# main_board_smd.net
KiCad netlist of a schematic drawn in EAGLE
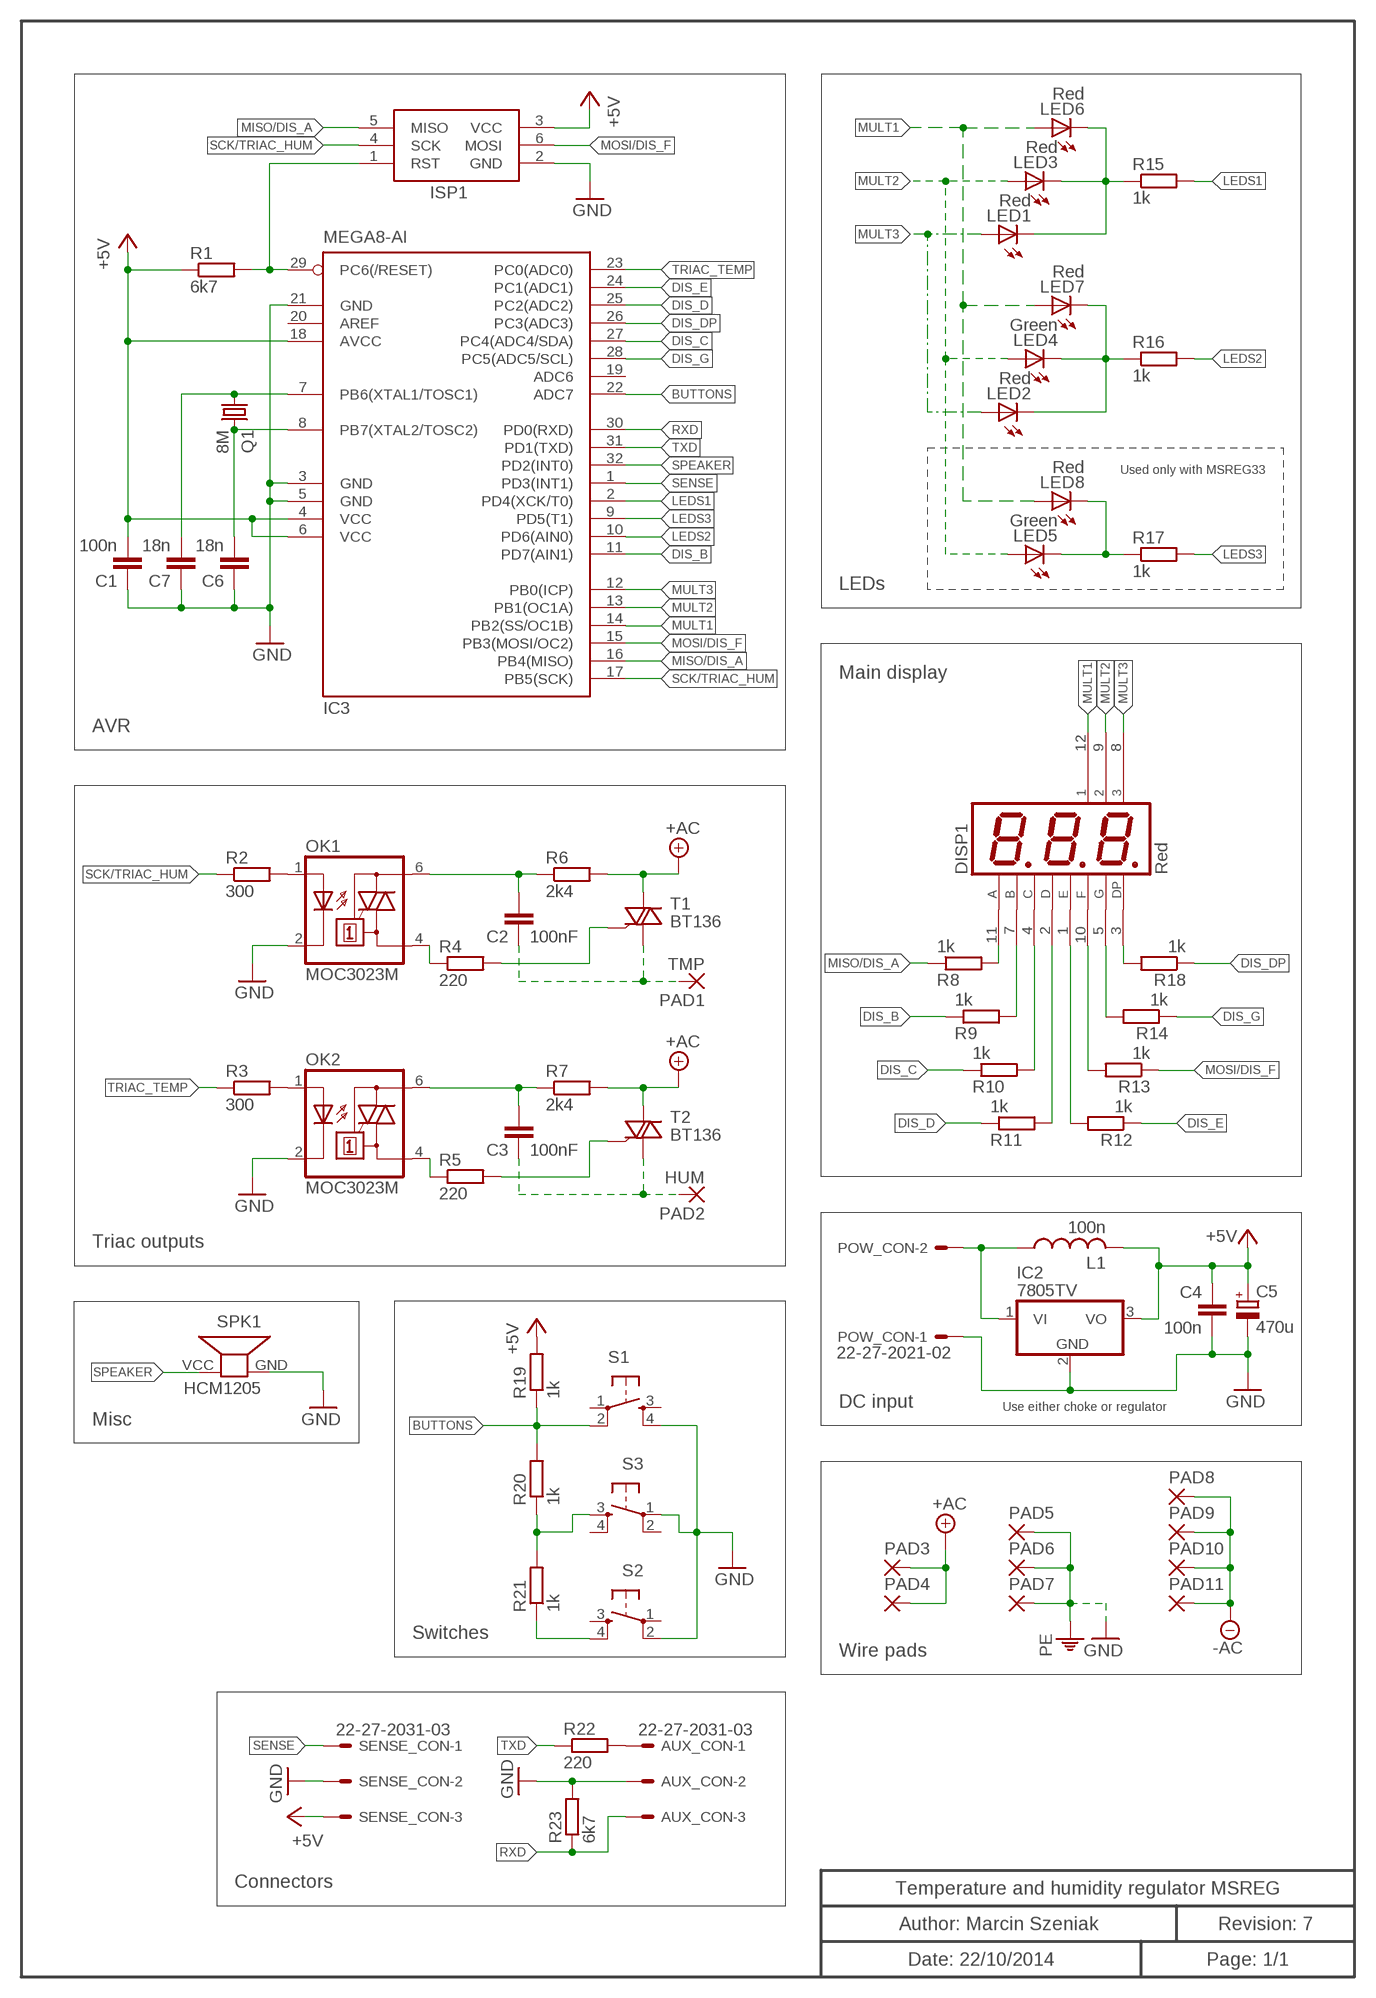
[diagram p0: schematic, sheet 1]

(export (version "E")
  (design (tool "Eeschema 10.0.6"))
  (components
    (comp (ref "AUX_CON")
      (value "22-27-2031-03")
      (footprint "eagle-import:6410-03")
      (libsource (lib "eagle-import") (part "22-?-0327-2031"))
    )
    (comp (ref "C1")
      (value "100n")
      (footprint "eagle-import:C2.5-4")
      (libsource (lib "eagle-import") (part "C2.5/4"))
    )
    (comp (ref "C2")
      (value "100nF")
      (footprint "eagle-import:C102-054X133")
      (libsource (lib "eagle-import") (part "C-EU102-054X133"))
    )
    (comp (ref "C3")
      (value "100nF")
      (footprint "eagle-import:C102-054X133")
      (libsource (lib "eagle-import") (part "C-EU102-054X133"))
    )
    (comp (ref "C4")
      (value "100n")
      (footprint "eagle-import:C2.5-2")
      (libsource (lib "eagle-import") (part "C2.5/2"))
    )
    (comp (ref "C5")
      (value "470u")
      (footprint "eagle-import:TT2D7")
      (libsource (lib "eagle-import") (part "CPOL-EUTT2D7"))
    )
    (comp (ref "C6")
      (value "18n")
      (footprint "eagle-import:C2.5-2")
      (libsource (lib "eagle-import") (part "C2.5/2"))
    )
    (comp (ref "C7")
      (value "18n")
      (footprint "eagle-import:C2.5-2")
      (libsource (lib "eagle-import") (part "C2.5/2"))
    )
    (comp (ref "DISP1")
      (value "Red")
      (footprint "eagle-import:7SEG3DIG")
      (libsource (lib "eagle-import") (part "7SEG3DIG"))
    )
    (comp (ref "IC2")
      (value "7805TV")
      (footprint "eagle-import:TO220V")
      (libsource (lib "eagle-import") (part "78TV05"))
    )
    (comp (ref "IC3")
      (value "MEGA8-AI")
      (footprint "eagle-import:TQFP32-08")
      (fields (field (name "MPN") "ATMEGA8-16AU"))
      (libsource (lib "eagle-import") (part "MEGA8-AI"))
    )
    (comp (ref "ISP1")
      (value "AVRISPAV")
      (footprint "eagle-import:AVRISP-KLOC")
      (libsource (lib "eagle-import") (part "AVRISPAV"))
    )
    (comp (ref "L1")
      (value "100n")
      (footprint "eagle-import:0204_7")
      (libsource (lib "eagle-import") (part "L-US0204/7"))
    )
    (comp (ref "LED1")
      (value "Red")
      (footprint "eagle-import:LED5MM")
      (libsource (lib "eagle-import") (part "LED5MM"))
    )
    (comp (ref "LED2")
      (value "Red")
      (footprint "eagle-import:LED5MM")
      (libsource (lib "eagle-import") (part "LED5MM"))
    )
    (comp (ref "LED3")
      (value "Red")
      (footprint "eagle-import:LED5MM")
      (libsource (lib "eagle-import") (part "LED5MM"))
    )
    (comp (ref "LED4")
      (value "Green")
      (footprint "eagle-import:LED5MM")
      (libsource (lib "eagle-import") (part "LED5MM"))
    )
    (comp (ref "LED5")
      (value "Green")
      (footprint "eagle-import:LED5MM")
      (libsource (lib "eagle-import") (part "LED5MM"))
    )
    (comp (ref "LED6")
      (value "Red")
      (footprint "eagle-import:LED5MM")
      (libsource (lib "eagle-import") (part "LED5MM"))
    )
    (comp (ref "LED7")
      (value "Red")
      (footprint "eagle-import:LED5MM")
      (libsource (lib "eagle-import") (part "LED5MM"))
    )
    (comp (ref "LED8")
      (value "Red")
      (footprint "eagle-import:LED5MM")
      (libsource (lib "eagle-import") (part "LED5MM"))
    )
    (comp (ref "OK1")
      (value "MOC3023M")
      (footprint "eagle-import:DIL06")
      (fields (field (name "MF") "FAIRCHILD SEMICONDUCTOR") (field (name "MPN") "MOC3023-M"))
      (libsource (lib "eagle-import") (part "MOC30M23"))
    )
    (comp (ref "OK2")
      (value "MOC3023M")
      (footprint "eagle-import:DIL06")
      (fields (field (name "MF") "FAIRCHILD SEMICONDUCTOR") (field (name "MPN") "MOC3023-M"))
      (libsource (lib "eagle-import") (part "MOC30M23"))
    )
    (comp (ref "PAD1")
      (value "TMP")
      (footprint "eagle-import:KLOCWIRE")
      (libsource (lib "eagle-import") (part "3,17/1,3KLOC"))
    )
    (comp (ref "PAD2")
      (value "HUM")
      (footprint "eagle-import:KLOCWIRE")
      (libsource (lib "eagle-import") (part "3,17/1,3KLOC"))
    )
    (comp (ref "PAD3")
      (value "3,17/1,3KLOC")
      (footprint "eagle-import:KLOCWIRE")
      (libsource (lib "eagle-import") (part "3,17/1,3KLOC"))
    )
    (comp (ref "PAD4")
      (value "3,17/1,3KLOC")
      (footprint "eagle-import:KLOCWIRE")
      (libsource (lib "eagle-import") (part "3,17/1,3KLOC"))
    )
    (comp (ref "PAD5")
      (value "3,17/1,3KLOC")
      (footprint "eagle-import:KLOCWIRE")
      (libsource (lib "eagle-import") (part "3,17/1,3KLOC"))
    )
    (comp (ref "PAD6")
      (value "3,17/1,3KLOC")
      (footprint "eagle-import:KLOCWIRE")
      (libsource (lib "eagle-import") (part "3,17/1,3KLOC"))
    )
    (comp (ref "PAD7")
      (value "3,17/1,3KLOC")
      (footprint "eagle-import:KLOCWIRE")
      (libsource (lib "eagle-import") (part "3,17/1,3KLOC"))
    )
    (comp (ref "PAD8")
      (value "3,17/1,3KLOC")
      (footprint "eagle-import:KLOCWIRE")
      (libsource (lib "eagle-import") (part "3,17/1,3KLOC"))
    )
    (comp (ref "PAD9")
      (value "3,17/1,3KLOC")
      (footprint "eagle-import:KLOCWIRE")
      (libsource (lib "eagle-import") (part "3,17/1,3KLOC"))
    )
    (comp (ref "PAD10")
      (value "3,17/1,3KLOC")
      (footprint "eagle-import:KLOCWIRE")
      (libsource (lib "eagle-import") (part "3,17/1,3KLOC"))
    )
    (comp (ref "PAD11")
      (value "3,17/1,3KLOC")
      (footprint "eagle-import:KLOCWIRE")
      (libsource (lib "eagle-import") (part "3,17/1,3KLOC"))
    )
    (comp (ref "POW_CON")
      (value "22-27-2021-02")
      (footprint "eagle-import:6410-02")
      (libsource (lib "eagle-import") (part "22-?-0227-2021"))
    )
    (comp (ref "Q1")
      (value "8M")
      (footprint "eagle-import:HC49U-V")
      (libsource (lib "eagle-import") (part "CRYSTALHC49U-V"))
    )
    (comp (ref "R1")
      (value "6k7")
      (footprint "eagle-import:0204_5")
      (libsource (lib "eagle-import") (part "R-EU_0204/5"))
    )
    (comp (ref "R2")
      (value "300")
      (footprint "eagle-import:0204_7")
      (libsource (lib "eagle-import") (part "R-EU_0204/7"))
    )
    (comp (ref "R3")
      (value "300")
      (footprint "eagle-import:0204_7")
      (libsource (lib "eagle-import") (part "R-EU_0204/7"))
    )
    (comp (ref "R4")
      (value "220")
      (footprint "eagle-import:0204_7")
      (libsource (lib "eagle-import") (part "R-EU_0204/7"))
    )
    (comp (ref "R5")
      (value "220")
      (footprint "eagle-import:0207_10")
      (libsource (lib "eagle-import") (part "R-EU_0207/10"))
    )
    (comp (ref "R6")
      (value "2k4")
      (footprint "eagle-import:0411V")
      (libsource (lib "eagle-import") (part "R-EU_0411/3V"))
    )
    (comp (ref "R7")
      (value "2k4")
      (footprint "eagle-import:0411_12")
      (libsource (lib "eagle-import") (part "R-EU_0411/12"))
    )
    (comp (ref "R8")
      (value "1k")
      (footprint "eagle-import:0204V")
      (libsource (lib "eagle-import") (part "R-EU_0204/2V"))
    )
    (comp (ref "R9")
      (value "1k")
      (footprint "eagle-import:0204V")
      (libsource (lib "eagle-import") (part "R-EU_0204/2V"))
    )
    (comp (ref "R10")
      (value "1k")
      (footprint "eagle-import:0204V")
      (libsource (lib "eagle-import") (part "R-EU_0204/2V"))
    )
    (comp (ref "R11")
      (value "1k")
      (footprint "eagle-import:0204V")
      (libsource (lib "eagle-import") (part "R-EU_0204/2V"))
    )
    (comp (ref "R12")
      (value "1k")
      (footprint "eagle-import:0204V")
      (libsource (lib "eagle-import") (part "R-EU_0204/2V"))
    )
    (comp (ref "R13")
      (value "1k")
      (footprint "eagle-import:0204V")
      (libsource (lib "eagle-import") (part "R-EU_0204/2V"))
    )
    (comp (ref "R14")
      (value "1k")
      (footprint "eagle-import:0204V")
      (libsource (lib "eagle-import") (part "R-EU_0204/2V"))
    )
    (comp (ref "R15")
      (value "1k")
      (footprint "eagle-import:0204_5")
      (libsource (lib "eagle-import") (part "R-EU_0204/5"))
    )
    (comp (ref "R16")
      (value "1k")
      (footprint "eagle-import:0204_5")
      (libsource (lib "eagle-import") (part "R-EU_0204/5"))
    )
    (comp (ref "R17")
      (value "1k")
      (footprint "eagle-import:0204_7")
      (libsource (lib "eagle-import") (part "R-EU_0204/7"))
    )
    (comp (ref "R18")
      (value "1k")
      (footprint "eagle-import:0204V")
      (libsource (lib "eagle-import") (part "R-EU_0204/2V"))
    )
    (comp (ref "R19")
      (value "1k")
      (footprint "eagle-import:0204_5")
      (libsource (lib "eagle-import") (part "R-EU_0204/5"))
    )
    (comp (ref "R20")
      (value "1k")
      (footprint "eagle-import:0204_5")
      (libsource (lib "eagle-import") (part "R-EU_0204/5"))
    )
    (comp (ref "R21")
      (value "1k")
      (footprint "eagle-import:0204_5")
      (libsource (lib "eagle-import") (part "R-EU_0204/5"))
    )
    (comp (ref "R22")
      (value "220")
      (footprint "eagle-import:0204_7")
      (libsource (lib "eagle-import") (part "R-EU_0204/7"))
    )
    (comp (ref "R23")
      (value "6k7")
      (footprint "eagle-import:0204_7")
      (libsource (lib "eagle-import") (part "R-EU_0204/7"))
    )
    (comp (ref "S1")
      (value "TAC_SWITCHPTH")
      (footprint "eagle-import:TACTILE-PTH")
      (libsource (lib "eagle-import") (part "TAC_SWITCHPTH"))
    )
    (comp (ref "S2")
      (value "TAC_SWITCHPTH")
      (footprint "eagle-import:TACTILE-PTH")
      (libsource (lib "eagle-import") (part "TAC_SWITCHPTH"))
    )
    (comp (ref "S3")
      (value "TAC_SWITCHPTH")
      (footprint "eagle-import:TACTILE-PTH")
      (libsource (lib "eagle-import") (part "TAC_SWITCHPTH"))
    )
    (comp (ref "SENSE_CON")
      (value "22-27-2031-03")
      (footprint "eagle-import:6410-03")
      (libsource (lib "eagle-import") (part "22-?-0327-2031"))
    )
    (comp (ref "SPK1")
      (value "HCM1205")
      (footprint "eagle-import:HCM12XX")
      (libsource (lib "eagle-import") (part "HCM1205"))
    )
    (comp (ref "T1")
      (value "BT136")
      (footprint "eagle-import:TRIAC_VE")
      (libsource (lib "eagle-import") (part "TRIAC"))
    )
    (comp (ref "T2")
      (value "BT136")
      (footprint "eagle-import:TRIAC_VE")
      (libsource (lib "eagle-import") (part "TRIAC"))
    )
  )
  (nets
    (net (code "1") (name "+5V") (class "Default")
      (node (ref "C1") (pin "2") (pinfunction "2_2") (pintype "passive"))
      (node (ref "C4") (pin "1") (pinfunction "1_1") (pintype "passive"))
      (node (ref "C5") (pin "+") (pinfunction "+_+") (pintype "passive"))
      (node (ref "IC2") (pin "3") (pinfunction "VO_3") (pintype "passive"))
      (node (ref "IC3") (pin "18") (pinfunction "AVCC_18") (pintype "power_in"))
      (node (ref "IC3") (pin "4") (pinfunction "VCC_4") (pintype "power_in"))
      (node (ref "IC3") (pin "6") (pinfunction "VCC_6") (pintype "power_in"))
      (node (ref "ISP1") (pin "3") (pinfunction "VCC_3") (pintype "power_in"))
      (node (ref "L1") (pin "2") (pinfunction "2_2") (pintype "passive"))
      (node (ref "R1") (pin "1") (pinfunction "1_1") (pintype "passive"))
      (node (ref "R19") (pin "2") (pinfunction "2_2") (pintype "passive"))
      (node (ref "SENSE_CON") (pin "3") (pinfunction "S_3") (pintype "passive"))
    )
    (net (code "2") (name "+AC") (class "Default")
      (node (ref "PAD3") (pin "1") (pinfunction "P_1") (pintype "passive"))
      (node (ref "PAD4") (pin "1") (pinfunction "P_1") (pintype "passive"))
      (node (ref "R6") (pin "2") (pinfunction "2_2") (pintype "passive"))
      (node (ref "R7") (pin "2") (pinfunction "2_2") (pintype "passive"))
      (node (ref "T1") (pin "A") (pinfunction "A2_A") (pintype "passive"))
      (node (ref "T2") (pin "A") (pinfunction "A2_A") (pintype "passive"))
    )
    (net (code "3") (name "-AC") (class "Default")
      (node (ref "PAD10") (pin "1") (pinfunction "P_1") (pintype "passive"))
      (node (ref "PAD11") (pin "1") (pinfunction "P_1") (pintype "passive"))
      (node (ref "PAD8") (pin "1") (pinfunction "P_1") (pintype "passive"))
      (node (ref "PAD9") (pin "1") (pinfunction "P_1") (pintype "passive"))
    )
    (net (code "4") (name "BUTTONS") (class "Default")
      (node (ref "IC3") (pin "22") (pinfunction "ADC7_22") (pintype "bidirectional"))
      (node (ref "R19") (pin "1") (pinfunction "1_1") (pintype "passive"))
      (node (ref "R20") (pin "2") (pinfunction "2_2") (pintype "passive"))
      (node (ref "S1") (pin "2") (pinfunction "2_2") (pintype "passive"))
    )
    (net (code "5") (name "DIS_B") (class "Default")
      (node (ref "IC3") (pin "11") (pinfunction "PD7(AIN1)_11") (pintype "bidirectional"))
      (node (ref "R9") (pin "1") (pinfunction "1_1") (pintype "passive"))
    )
    (net (code "6") (name "DIS_C") (class "Default")
      (node (ref "IC3") (pin "27") (pinfunction "PC4(ADC4/SDA)_27") (pintype "bidirectional"))
      (node (ref "R10") (pin "1") (pinfunction "1_1") (pintype "passive"))
    )
    (net (code "7") (name "DIS_D") (class "Default")
      (node (ref "IC3") (pin "25") (pinfunction "PC2(ADC2)_25") (pintype "bidirectional"))
      (node (ref "R11") (pin "1") (pinfunction "1_1") (pintype "passive"))
    )
    (net (code "8") (name "DIS_DP") (class "Default")
      (node (ref "IC3") (pin "26") (pinfunction "PC3(ADC3)_26") (pintype "bidirectional"))
      (node (ref "R18") (pin "1") (pinfunction "1_1") (pintype "passive"))
    )
    (net (code "9") (name "DIS_E") (class "Default")
      (node (ref "IC3") (pin "24") (pinfunction "PC1(ADC1)_24") (pintype "bidirectional"))
      (node (ref "R12") (pin "1") (pinfunction "1_1") (pintype "passive"))
    )
    (net (code "10") (name "DIS_G") (class "Default")
      (node (ref "IC3") (pin "28") (pinfunction "PC5(ADC5/SCL)_28") (pintype "bidirectional"))
      (node (ref "R14") (pin "1") (pinfunction "1_1") (pintype "passive"))
    )
    (net (code "11") (name "GND") (class "Default")
      (node (ref "AUX_CON") (pin "2") (pinfunction "S_2") (pintype "passive"))
      (node (ref "C1") (pin "1") (pinfunction "1_1") (pintype "passive"))
      (node (ref "C4") (pin "2") (pinfunction "2_2") (pintype "passive"))
      (node (ref "C5") (pin "-") (pinfunction "-_-") (pintype "passive"))
      (node (ref "C6") (pin "1") (pinfunction "1_1") (pintype "passive"))
      (node (ref "C7") (pin "1") (pinfunction "1_1") (pintype "passive"))
      (node (ref "IC2") (pin "2") (pinfunction "GND_2") (pintype "passive"))
      (node (ref "IC3") (pin "21") (pinfunction "GND_21") (pintype "power_in"))
      (node (ref "IC3") (pin "3") (pinfunction "GND_3") (pintype "power_in"))
      (node (ref "IC3") (pin "5") (pinfunction "GND_5") (pintype "power_in"))
      (node (ref "ISP1") (pin "2") (pinfunction "GND_2") (pintype "power_in"))
      (node (ref "OK1") (pin "2") (pinfunction "C_2") (pintype "passive"))
      (node (ref "OK2") (pin "2") (pinfunction "C_2") (pintype "passive"))
      (node (ref "PAD5") (pin "1") (pinfunction "P_1") (pintype "passive"))
      (node (ref "PAD6") (pin "1") (pinfunction "P_1") (pintype "passive"))
      (node (ref "PAD7") (pin "1") (pinfunction "P_1") (pintype "passive"))
      (node (ref "POW_CON") (pin "1") (pinfunction "S_1") (pintype "passive"))
      (node (ref "R23") (pin "2") (pinfunction "2_2") (pintype "passive"))
      (node (ref "S1") (pin "4") (pinfunction "4_4") (pintype "passive"))
      (node (ref "S2") (pin "2") (pinfunction "2_2") (pintype "passive"))
      (node (ref "S3") (pin "1") (pinfunction "1_1") (pintype "passive"))
      (node (ref "SENSE_CON") (pin "2") (pinfunction "S_2") (pintype "passive"))
      (node (ref "SPK1") (pin "GND") (pinfunction "GND_GND") (pintype "power_in"))
    )
    (net (code "12") (name "LEDS1") (class "Default")
      (node (ref "IC3") (pin "2") (pinfunction "PD4(XCK/T0)_2") (pintype "bidirectional"))
      (node (ref "R15") (pin "2") (pinfunction "2_2") (pintype "passive"))
    )
    (net (code "13") (name "LEDS2") (class "Default")
      (node (ref "IC3") (pin "10") (pinfunction "PD6(AIN0)_10") (pintype "bidirectional"))
      (node (ref "R16") (pin "2") (pinfunction "2_2") (pintype "passive"))
    )
    (net (code "14") (name "LEDS3") (class "Default")
      (node (ref "IC3") (pin "9") (pinfunction "PD5(T1)_9") (pintype "bidirectional"))
      (node (ref "R17") (pin "2") (pinfunction "2_2") (pintype "passive"))
    )
    (net (code "15") (name "MISO{slash}DIS_A") (class "Default")
      (node (ref "IC3") (pin "16") (pinfunction "PB4(MISO)_16") (pintype "bidirectional"))
      (node (ref "ISP1") (pin "5") (pinfunction "MISO_5") (pintype "input"))
      (node (ref "R8") (pin "1") (pinfunction "1_1") (pintype "passive"))
    )
    (net (code "16") (name "MOSI{slash}DIS_F") (class "Default")
      (node (ref "IC3") (pin "15") (pinfunction "PB3(MOSI/OC2)_15") (pintype "bidirectional"))
      (node (ref "ISP1") (pin "6") (pinfunction "MOSI_6") (pintype "output"))
      (node (ref "R13") (pin "1") (pinfunction "1_1") (pintype "passive"))
    )
    (net (code "17") (name "MULT1") (class "Default")
      (node (ref "DISP1") (pin "12") (pinfunction "1_12") (pintype "passive"))
      (node (ref "IC3") (pin "14") (pinfunction "PB2(SS/OC1B)_14") (pintype "bidirectional"))
      (node (ref "LED6") (pin "A") (pinfunction "A_A") (pintype "passive"))
      (node (ref "LED7") (pin "A") (pinfunction "A_A") (pintype "passive"))
      (node (ref "LED8") (pin "A") (pinfunction "A_A") (pintype "passive"))
    )
    (net (code "18") (name "MULT2") (class "Default")
      (node (ref "DISP1") (pin "9") (pinfunction "2_9") (pintype "passive"))
      (node (ref "IC3") (pin "13") (pinfunction "PB1(OC1A)_13") (pintype "bidirectional"))
      (node (ref "LED3") (pin "A") (pinfunction "A_A") (pintype "passive"))
      (node (ref "LED4") (pin "A") (pinfunction "A_A") (pintype "passive"))
      (node (ref "LED5") (pin "A") (pinfunction "A_A") (pintype "passive"))
    )
    (net (code "19") (name "MULT3") (class "Default")
      (node (ref "DISP1") (pin "8") (pinfunction "3_8") (pintype "passive"))
      (node (ref "IC3") (pin "12") (pinfunction "PB0(ICP)_12") (pintype "bidirectional"))
      (node (ref "LED1") (pin "A") (pinfunction "A_A") (pintype "passive"))
      (node (ref "LED2") (pin "A") (pinfunction "A_A") (pintype "passive"))
    )
    (net (code "20") (name "Net-(AUX_CONA-S)") (class "Default")
      (node (ref "AUX_CON") (pin "1") (pinfunction "S_1") (pintype "passive"))
      (node (ref "R22") (pin "2") (pinfunction "2_2") (pintype "passive"))
    )
    (net (code "21") (name "Net-(DISP1-A)") (class "Default")
      (node (ref "DISP1") (pin "11") (pinfunction "A_11") (pintype "passive"))
      (node (ref "R8") (pin "2") (pinfunction "2_2") (pintype "passive"))
    )
    (net (code "22") (name "Net-(DISP1-B)") (class "Default")
      (node (ref "DISP1") (pin "7") (pinfunction "B_7") (pintype "passive"))
      (node (ref "R9") (pin "2") (pinfunction "2_2") (pintype "passive"))
    )
    (net (code "23") (name "Net-(DISP1-C)") (class "Default")
      (node (ref "DISP1") (pin "4") (pinfunction "C_4") (pintype "passive"))
      (node (ref "R10") (pin "2") (pinfunction "2_2") (pintype "passive"))
    )
    (net (code "24") (name "Net-(DISP1-D)") (class "Default")
      (node (ref "DISP1") (pin "2") (pinfunction "D_2") (pintype "passive"))
      (node (ref "R11") (pin "2") (pinfunction "2_2") (pintype "passive"))
    )
    (net (code "25") (name "Net-(DISP1-DP)") (class "Default")
      (node (ref "DISP1") (pin "3") (pinfunction "DP_3") (pintype "passive"))
      (node (ref "R18") (pin "2") (pinfunction "2_2") (pintype "passive"))
    )
    (net (code "26") (name "Net-(DISP1-E)") (class "Default")
      (node (ref "DISP1") (pin "1") (pinfunction "E_1") (pintype "passive"))
      (node (ref "R12") (pin "2") (pinfunction "2_2") (pintype "passive"))
    )
    (net (code "27") (name "Net-(DISP1-F)") (class "Default")
      (node (ref "DISP1") (pin "10") (pinfunction "F_10") (pintype "passive"))
      (node (ref "R13") (pin "2") (pinfunction "2_2") (pintype "passive"))
    )
    (net (code "28") (name "Net-(DISP1-G)") (class "Default")
      (node (ref "DISP1") (pin "5") (pinfunction "G_5") (pintype "passive"))
      (node (ref "R14") (pin "2") (pinfunction "2_2") (pintype "passive"))
    )
    (net (code "29") (name "Net-(IC2-VI)") (class "Default")
      (node (ref "IC2") (pin "1") (pinfunction "VI_1") (pintype "input"))
      (node (ref "L1") (pin "1") (pinfunction "1_1") (pintype "passive"))
      (node (ref "POW_CON") (pin "2") (pinfunction "S_2") (pintype "passive"))
    )
    (net (code "30") (name "Net-(IC3-PB6(XTAL1{slash}TOSC1))") (class "Default")
      (node (ref "C7") (pin "2") (pinfunction "2_2") (pintype "passive"))
      (node (ref "IC3") (pin "7") (pinfunction "PB6(XTAL1/TOSC1)_7") (pintype "bidirectional"))
      (node (ref "Q1") (pin "1") (pinfunction "1_1") (pintype "passive"))
    )
    (net (code "31") (name "Net-(IC3-PB7(XTAL2{slash}TOSC2))") (class "Default")
      (node (ref "C6") (pin "2") (pinfunction "2_2") (pintype "passive"))
      (node (ref "IC3") (pin "8") (pinfunction "PB7(XTAL2/TOSC2)_8") (pintype "bidirectional"))
      (node (ref "Q1") (pin "2") (pinfunction "2_2") (pintype "passive"))
    )
    (net (code "32") (name "Net-(IC3-PC6({slash}RESET))") (class "Default")
      (node (ref "IC3") (pin "29") (pinfunction "PC6(/RESET)_29") (pintype "bidirectional"))
      (node (ref "ISP1") (pin "1") (pinfunction "RST_1") (pintype "output"))
      (node (ref "R1") (pin "2") (pinfunction "2_2") (pintype "passive"))
    )
    (net (code "33") (name "Net-(LED1-C)") (class "Default")
      (node (ref "LED1") (pin "K") (pinfunction "C_K") (pintype "passive"))
      (node (ref "LED3") (pin "K") (pinfunction "C_K") (pintype "passive"))
      (node (ref "LED6") (pin "K") (pinfunction "C_K") (pintype "passive"))
      (node (ref "R15") (pin "1") (pinfunction "1_1") (pintype "passive"))
    )
    (net (code "34") (name "Net-(LED2-C)") (class "Default")
      (node (ref "LED2") (pin "K") (pinfunction "C_K") (pintype "passive"))
      (node (ref "LED4") (pin "K") (pinfunction "C_K") (pintype "passive"))
      (node (ref "LED7") (pin "K") (pinfunction "C_K") (pintype "passive"))
      (node (ref "R16") (pin "1") (pinfunction "1_1") (pintype "passive"))
    )
    (net (code "35") (name "Net-(LED5-C)") (class "Default")
      (node (ref "LED5") (pin "K") (pinfunction "C_K") (pintype "passive"))
      (node (ref "LED8") (pin "K") (pinfunction "C_K") (pintype "passive"))
      (node (ref "R17") (pin "1") (pinfunction "1_1") (pintype "passive"))
    )
    (net (code "36") (name "Net-(OK1-A)") (class "Default")
      (node (ref "OK1") (pin "1") (pinfunction "A_1") (pintype "passive"))
      (node (ref "R2") (pin "2") (pinfunction "2_2") (pintype "passive"))
    )
    (net (code "37") (name "Net-(OK1-A1)") (class "Default")
      (node (ref "OK1") (pin "4") (pinfunction "A1_4") (pintype "passive"))
      (node (ref "R4") (pin "1") (pinfunction "1_1") (pintype "passive"))
    )
    (net (code "38") (name "Net-(OK1-A2)") (class "Default")
      (node (ref "C2") (pin "1") (pinfunction "1_1") (pintype "passive"))
      (node (ref "OK1") (pin "6") (pinfunction "A2_6") (pintype "passive"))
      (node (ref "R6") (pin "1") (pinfunction "1_1") (pintype "passive"))
    )
    (net (code "39") (name "Net-(OK2-A)") (class "Default")
      (node (ref "OK2") (pin "1") (pinfunction "A_1") (pintype "passive"))
      (node (ref "R3") (pin "2") (pinfunction "2_2") (pintype "passive"))
    )
    (net (code "40") (name "Net-(OK2-A1)") (class "Default")
      (node (ref "OK2") (pin "4") (pinfunction "A1_4") (pintype "passive"))
      (node (ref "R5") (pin "1") (pinfunction "1_1") (pintype "passive"))
    )
    (net (code "41") (name "Net-(OK2-A2)") (class "Default")
      (node (ref "C3") (pin "1") (pinfunction "1_1") (pintype "passive"))
      (node (ref "OK2") (pin "6") (pinfunction "A2_6") (pintype "passive"))
      (node (ref "R7") (pin "1") (pinfunction "1_1") (pintype "passive"))
    )
    (net (code "42") (name "Net-(PAD1-P)") (class "Default")
      (node (ref "C2") (pin "2") (pinfunction "2_2") (pintype "passive"))
      (node (ref "PAD1") (pin "1") (pinfunction "P_1") (pintype "passive"))
      (node (ref "T1") (pin "C") (pinfunction "A1_C") (pintype "passive"))
    )
    (net (code "43") (name "Net-(PAD2-P)") (class "Default")
      (node (ref "C3") (pin "2") (pinfunction "2_2") (pintype "passive"))
      (node (ref "PAD2") (pin "1") (pinfunction "P_1") (pintype "passive"))
      (node (ref "T2") (pin "C") (pinfunction "A1_C") (pintype "passive"))
    )
    (net (code "44") (name "Net-(R4-Pad2)") (class "Default")
      (node (ref "R4") (pin "2") (pinfunction "2_2") (pintype "passive"))
      (node (ref "T1") (pin "G") (pinfunction "G_G") (pintype "passive"))
    )
    (net (code "45") (name "Net-(R5-Pad2)") (class "Default")
      (node (ref "R5") (pin "2") (pinfunction "2_2") (pintype "passive"))
      (node (ref "T2") (pin "G") (pinfunction "G_G") (pintype "passive"))
    )
    (net (code "46") (name "Net-(R20-Pad1)") (class "Default")
      (node (ref "R20") (pin "1") (pinfunction "1_1") (pintype "passive"))
      (node (ref "R21") (pin "2") (pinfunction "2_2") (pintype "passive"))
      (node (ref "S3") (pin "3") (pinfunction "3_3") (pintype "passive"))
    )
    (net (code "47") (name "Net-(R21-Pad1)") (class "Default")
      (node (ref "R21") (pin "1") (pinfunction "1_1") (pintype "passive"))
      (node (ref "S2") (pin "4") (pinfunction "4_4") (pintype "passive"))
    )
    (net (code "48") (name "RXD") (class "Default")
      (node (ref "AUX_CON") (pin "3") (pinfunction "S_3") (pintype "passive"))
      (node (ref "IC3") (pin "30") (pinfunction "PD0(RXD)_30") (pintype "bidirectional"))
      (node (ref "R23") (pin "1") (pinfunction "1_1") (pintype "passive"))
    )
    (net (code "49") (name "SCK{slash}TRIAC_HUM") (class "Default")
      (node (ref "IC3") (pin "17") (pinfunction "PB5(SCK)_17") (pintype "bidirectional"))
      (node (ref "ISP1") (pin "4") (pinfunction "SCK_4") (pintype "output"))
      (node (ref "R2") (pin "1") (pinfunction "1_1") (pintype "passive"))
    )
    (net (code "50") (name "SENSE") (class "Default")
      (node (ref "IC3") (pin "1") (pinfunction "PD3(INT1)_1") (pintype "bidirectional"))
      (node (ref "SENSE_CON") (pin "1") (pinfunction "S_1") (pintype "passive"))
    )
    (net (code "51") (name "SPEAKER") (class "Default")
      (node (ref "IC3") (pin "32") (pinfunction "PD2(INT0)_32") (pintype "bidirectional"))
      (node (ref "SPK1") (pin "VCC") (pinfunction "VCC_VCC") (pintype "power_in"))
    )
    (net (code "52") (name "TRIAC_TEMP") (class "Default")
      (node (ref "IC3") (pin "23") (pinfunction "PC0(ADC0)_23") (pintype "bidirectional"))
      (node (ref "R3") (pin "1") (pinfunction "1_1") (pintype "passive"))
    )
    (net (code "53") (name "TXD") (class "Default")
      (node (ref "IC3") (pin "31") (pinfunction "PD1(TXD)_31") (pintype "bidirectional"))
      (node (ref "R22") (pin "1") (pinfunction "1_1") (pintype "passive"))
    )
    (net (code "54") (name "unconnected-(IC3-ADC6-Pad19)") (class "Default")
      (node (ref "IC3") (pin "19") (pinfunction "ADC6_19") (pintype "bidirectional"))
    )
    (net (code "55") (name "unconnected-(IC3-AREF-Pad20)") (class "Default")
      (node (ref "IC3") (pin "20") (pinfunction "AREF_20") (pintype "passive"))
    )
    (net (code "56") (name "unconnected-(S1-Pad1)") (class "Default")
      (node (ref "S1") (pin "1") (pinfunction "1_1") (pintype "passive"))
    )
    (net (code "57") (name "unconnected-(S1-Pad3)") (class "Default")
      (node (ref "S1") (pin "3") (pinfunction "3_3") (pintype "passive"))
    )
    (net (code "58") (name "unconnected-(S2-Pad1)") (class "Default")
      (node (ref "S2") (pin "1") (pinfunction "1_1") (pintype "passive"))
    )
    (net (code "59") (name "unconnected-(S2-Pad3)") (class "Default")
      (node (ref "S2") (pin "3") (pinfunction "3_3") (pintype "passive"))
    )
    (net (code "60") (name "unconnected-(S3-Pad2)") (class "Default")
      (node (ref "S3") (pin "2") (pinfunction "2_2") (pintype "passive"))
    )
    (net (code "61") (name "unconnected-(S3-Pad4)") (class "Default")
      (node (ref "S3") (pin "4") (pinfunction "4_4") (pintype "passive"))
    )
  )
)
